# Charge_Station.net
KiCad netlist of a schematic drawn in Altium Designer
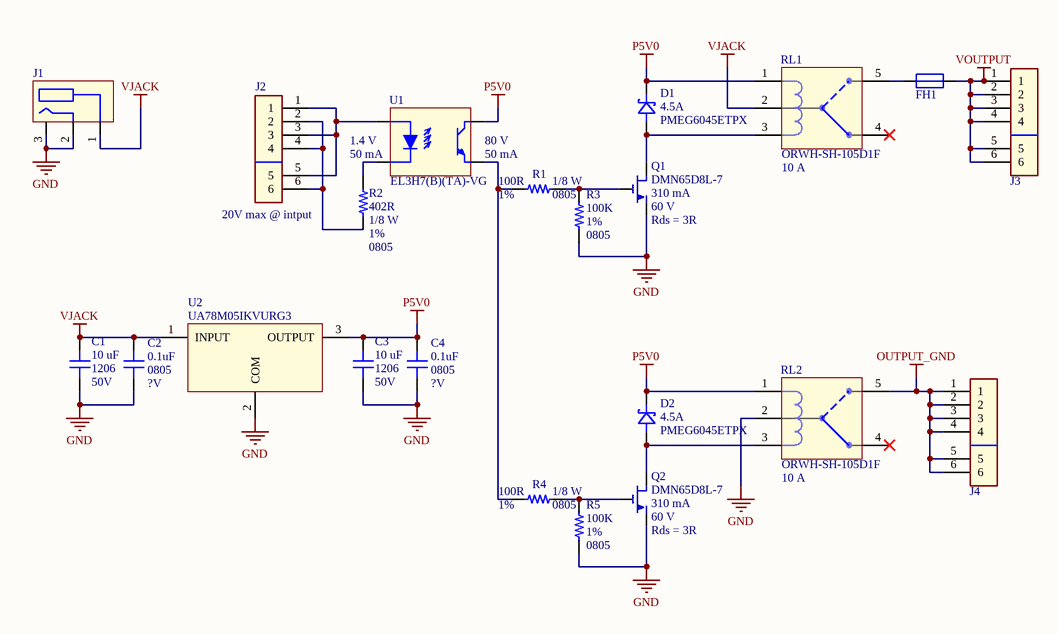
[diagram p0: Charge Station.SchDoc]

(export (version "E")
  (design (tool "Eeschema 10.0.6"))
  (components
    (comp (ref "C1")
      (value "10 uF")
      (footprint "CAP_1206")
      (description "CAP - 1206")
      (fields
        (field (name "PACKAGE") "1206")
        (field (name "VOLTAGE") "50V")
        (field (name "PART NUMBER") "GRT31CR61H106ME01L")
      )
      (libsource (lib "SecureBot") (part "CAP - 1206"))
    )
    (comp (ref "C2")
      (value "0.1uF")
      (footprint "CAP_0805")
      (description "CAP - 0805")
      (fields
        (field (name "PART NUMBER") "CC0805KRX7R9BB104")
        (field (name "PACKAGE") "0805")
        (field (name "VOLTAGE") "?V")
      )
      (libsource (lib "SecureBot") (part "CAP - 0805"))
    )
    (comp (ref "C3")
      (value "10 uF")
      (footprint "CAP_1206")
      (description "CAP - 1206")
      (fields
        (field (name "PACKAGE") "1206")
        (field (name "VOLTAGE") "50V")
        (field (name "PART NUMBER") "GRT31CR61H106ME01L")
      )
      (libsource (lib "SecureBot") (part "CAP - 1206"))
    )
    (comp (ref "C4")
      (value "0.1uF")
      (footprint "CAP_0805")
      (description "CAP - 0805")
      (fields
        (field (name "PART NUMBER") "CC0805KRX7R9BB104")
        (field (name "PACKAGE") "0805")
        (field (name "VOLTAGE") "?V")
      )
      (libsource (lib "SecureBot") (part "CAP - 0805"))
    )
    (comp (ref "D1")
      (value "SCHOTTKEY")
      (footprint "DO-214AC_SOD128")
      (fields (field (name "CURRENT") "4.5A") (field (name "PART NUMBER") "PMEG6045ETPX"))
      (libsource (lib "SecureBot") (part "SCHOTTKEY"))
    )
    (comp (ref "D2")
      (value "SCHOTTKEY")
      (footprint "DO-214AC_SOD128")
      (fields (field (name "CURRENT") "4.5A") (field (name "PART NUMBER") "PMEG6045ETPX"))
      (libsource (lib "SecureBot") (part "SCHOTTKEY"))
    )
    (comp (ref "FH1")
      (value "FH 3AB-3AG")
      (footprint "FH_3AB_3AG")
      (description "Fuse holder (3AB-3AG)")
      (fields (field (name "PART NUMBER") "01020071Z x2"))
      (libsource (lib "SecureBot") (part "FH 3AB-3AG"))
    )
    (comp (ref "J1")
      (value "Barrel 5.5x2.5mm")
      (footprint "Barrel 5.5mm 2.5mm")
      (description "Jack 5.5x2.5mm")
      (fields (field (name "PART NUMBER") "PJ-082BH"))
      (libsource (lib "SecureBot") (part "Barrel 5.5x2.5mm"))
    )
    (comp (ref "J2")
      (value "MOLEX 4 POS - TERMINAL BLOCK 2 POS")
      (footprint "MOLEX4POS_TERMBLOCK2POS")
      (fields (field (name "PART NUMBER") "0039281043") (field (name "PART NUMBER_1") "OSTOQ023250"))
      (libsource (lib "") (part "MOLEX 4 POS - TERMINAL BLOCK 2 POS_1"))
    )
    (comp (ref "J3")
      (value "MOLEX 4 POS - TERMINAL BLOCK 2 POS")
      (footprint "MOLEX4POS_TERMBLOCK2POS")
      (fields (field (name "PART NUMBER") "0039281043") (field (name "PART NUMBER_1") "OSTOQ023250"))
      (libsource (lib "SecureBot") (part "MOLEX 4 POS - TERMINAL BLOCK 2 POS"))
    )
    (comp (ref "J4")
      (value "MOLEX 4 POS - TERMINAL BLOCK 2 POS")
      (footprint "MOLEX4POS_TERMBLOCK2POS")
      (fields (field (name "PART NUMBER") "0039281043") (field (name "PART NUMBER_1") "OSTOQ023250"))
      (libsource (lib "SecureBot") (part "MOLEX 4 POS - TERMINAL BLOCK 2 POS"))
    )
    (comp (ref "Q1")
      (value "NMOS")
      (footprint "SOT-23")
      (fields
        (field (name "PART NUMBER") "DMN65D8L-7")
        (field (name "A MAX") "310 mA")
        (field (name "VDS MAX") "60 V")
        (field (name "RON") "Rds = 3R")
      )
      (libsource (lib "SecureBot") (part "NMOS"))
    )
    (comp (ref "Q2")
      (value "NMOS")
      (footprint "SOT-23")
      (fields
        (field (name "PART NUMBER") "DMN65D8L-7")
        (field (name "A MAX") "310 mA")
        (field (name "VDS MAX") "60 V")
        (field (name "RON") "Rds = 3R")
      )
      (libsource (lib "SecureBot") (part "NMOS"))
    )
    (comp (ref "R1")
      (value "100R")
      (footprint "RES_0805")
      (description "RES - 0805")
      (fields
        (field (name "PART NUMBER") "ERA-6AEB101V")
        (field (name "WATT") "1/8 W")
        (field (name "TOLERANCE") "1%")
        (field (name "PACKAGE") "0805")
      )
      (libsource (lib "SecureBot") (part "RES - 0805"))
    )
    (comp (ref "R2")
      (value "402R")
      (footprint "RES_0805")
      (description "RES - 0805")
      (fields
        (field (name "PART NUMBER") "ERA-6AEB4020V")
        (field (name "WATT") "1/8 W")
        (field (name "TOLERANCE") "1%")
        (field (name "PACKAGE") "0805")
      )
      (libsource (lib "SecureBot") (part "RES - 0805"))
    )
    (comp (ref "R3")
      (value "100K")
      (footprint "RES_0805")
      (description "RES - 0805")
      (fields
        (field (name "PART NUMBER") "RMCF0805FT100K")
        (field (name "TOLERANCE") "1%")
        (field (name "PACKAGE") "0805")
      )
      (libsource (lib "SecureBot") (part "RES - 0805"))
    )
    (comp (ref "R4")
      (value "100R")
      (footprint "RES_0805")
      (description "RES - 0805")
      (fields
        (field (name "PART NUMBER") "ERA-6AEB101V")
        (field (name "WATT") "1/8 W")
        (field (name "TOLERANCE") "1%")
        (field (name "PACKAGE") "0805")
      )
      (libsource (lib "SecureBot") (part "RES - 0805"))
    )
    (comp (ref "R5")
      (value "100K")
      (footprint "RES_0805")
      (description "RES - 0805")
      (fields
        (field (name "PART NUMBER") "RMCF0805FT100K")
        (field (name "TOLERANCE") "1%")
        (field (name "PACKAGE") "0805")
      )
      (libsource (lib "SecureBot") (part "RES - 0805"))
    )
    (comp (ref "RL1")
      (value "Relay SPDT")
      (footprint "ORWH-SH")
      (fields (field (name "PART NUMBER") "ORWH-SH-105D1F") (field (name "A MAX") "10 A"))
      (libsource (lib "SecureBot") (part "Relay SPDT"))
    )
    (comp (ref "RL2")
      (value "Relay SPDT")
      (footprint "ORWH-SH")
      (fields (field (name "PART NUMBER") "ORWH-SH-105D1F") (field (name "A MAX") "10 A"))
      (libsource (lib "SecureBot") (part "Relay SPDT"))
    )
    (comp (ref "U1")
      (value "Optoisolator")
      (footprint "SOIC127P700X200-4M")
      (fields
        (field (name "PART NUMBER") "EL3H7(B)(TA)-VG")
        (field (name "MAX VF") "1.4 V")
        (field (name "MAX OUTPUT CURRENT") "50 mA")
        (field (name "VOUTPUT MAX") "80 V")
        (field (name "MAX IF") "50 mA")
      )
      (libsource (lib "SecureBot") (part "Optoisolator"))
    )
    (comp (ref "U2")
      (value "UA78M")
      (footprint "DPAK229P991X252-3N")
      (fields (field (name "PART NUMBER") "UA78M05IKVURG3"))
      (libsource (lib "SecureBot") (part "UA78M"))
    )
  )
  (nets
    (net (code "1") (name "GND") (class "Default")
      (node (ref "C1") (pin "2") (pinfunction "2_2") (pintype "passive"))
      (node (ref "C2") (pin "2") (pinfunction "2_2") (pintype "passive"))
      (node (ref "C3") (pin "2") (pinfunction "2_2") (pintype "passive"))
      (node (ref "C4") (pin "2") (pinfunction "2_2") (pintype "passive"))
      (node (ref "J1") (pin "2") (pinfunction "2_2") (pintype "passive"))
      (node (ref "J1") (pin "3") (pinfunction "3_3") (pintype "passive"))
      (node (ref "Q1") (pin "1") (pinfunction "1_1") (pintype "passive"))
      (node (ref "Q2") (pin "1") (pinfunction "1_1") (pintype "passive"))
      (node (ref "R3") (pin "1") (pinfunction "1_1") (pintype "passive"))
      (node (ref "R5") (pin "1") (pinfunction "1_1") (pintype "passive"))
      (node (ref "RL2") (pin "2") (pinfunction "2_2") (pintype "passive"))
      (node (ref "U2") (pin "2") (pinfunction "COM_2") (pintype "passive"))
    )
    (net (code "2") (name "Net-(D1-Pad1)") (class "Default")
      (node (ref "D1") (pin "1") (pinfunction "1_1") (pintype "passive"))
      (node (ref "Q1") (pin "3") (pinfunction "3_3") (pintype "passive"))
      (node (ref "RL1") (pin "3") (pinfunction "3_3") (pintype "passive"))
    )
    (net (code "3") (name "Net-(D2-Pad1)") (class "Default")
      (node (ref "D2") (pin "1") (pinfunction "1_1") (pintype "passive"))
      (node (ref "Q2") (pin "3") (pinfunction "3_3") (pintype "passive"))
      (node (ref "RL2") (pin "3") (pinfunction "3_3") (pintype "passive"))
    )
    (net (code "4") (name "Net-(FH1-Pad2)") (class "Default")
      (node (ref "FH1") (pin "2") (pinfunction "2_2") (pintype "passive"))
      (node (ref "RL1") (pin "5") (pinfunction "5_5") (pintype "passive"))
    )
    (net (code "5") (name "Net-(J2-Pad1)") (class "Default")
      (node (ref "J2") (pin "1") (pinfunction "1_1") (pintype "passive"))
      (node (ref "J2") (pin "3") (pinfunction "3_3") (pintype "passive"))
      (node (ref "J2") (pin "5") (pinfunction "5_5") (pintype "passive"))
      (node (ref "U1") (pin "1") (pinfunction "1_1") (pintype "passive"))
    )
    (net (code "6") (name "Net-(J2-Pad2)") (class "Default")
      (node (ref "J2") (pin "2") (pinfunction "2_2") (pintype "passive"))
      (node (ref "J2") (pin "4") (pinfunction "4_4") (pintype "passive"))
      (node (ref "J2") (pin "6") (pinfunction "6_6") (pintype "passive"))
      (node (ref "R2") (pin "1") (pinfunction "1_1") (pintype "passive"))
    )
    (net (code "7") (name "Net-(Q1-Pad2)") (class "Default")
      (node (ref "Q1") (pin "2") (pinfunction "2_2") (pintype "passive"))
      (node (ref "R1") (pin "2") (pinfunction "2_2") (pintype "passive"))
      (node (ref "R3") (pin "2") (pinfunction "2_2") (pintype "passive"))
    )
    (net (code "8") (name "Net-(Q2-Pad2)") (class "Default")
      (node (ref "Q2") (pin "2") (pinfunction "2_2") (pintype "passive"))
      (node (ref "R4") (pin "2") (pinfunction "2_2") (pintype "passive"))
      (node (ref "R5") (pin "2") (pinfunction "2_2") (pintype "passive"))
    )
    (net (code "9") (name "Net-(R1-Pad1)") (class "Default")
      (node (ref "R1") (pin "1") (pinfunction "1_1") (pintype "passive"))
      (node (ref "R4") (pin "1") (pinfunction "1_1") (pintype "passive"))
      (node (ref "U1") (pin "3") (pinfunction "3_3") (pintype "passive"))
    )
    (net (code "10") (name "Net-(R2-Pad2)") (class "Default")
      (node (ref "R2") (pin "2") (pinfunction "2_2") (pintype "passive"))
      (node (ref "U1") (pin "2") (pinfunction "2_2") (pintype "passive"))
    )
    (net (code "11") (name "OUTPUT_GND") (class "Default")
      (node (ref "J4") (pin "1") (pinfunction "1_1") (pintype "passive"))
      (node (ref "J4") (pin "2") (pinfunction "2_2") (pintype "passive"))
      (node (ref "J4") (pin "3") (pinfunction "3_3") (pintype "passive"))
      (node (ref "J4") (pin "4") (pinfunction "4_4") (pintype "passive"))
      (node (ref "J4") (pin "5") (pinfunction "5_5") (pintype "passive"))
      (node (ref "J4") (pin "6") (pinfunction "6_6") (pintype "passive"))
      (node (ref "RL2") (pin "5") (pinfunction "5_5") (pintype "passive"))
    )
    (net (code "12") (name "P5V0") (class "Default")
      (node (ref "C3") (pin "1") (pinfunction "1_1") (pintype "passive"))
      (node (ref "C4") (pin "1") (pinfunction "1_1") (pintype "passive"))
      (node (ref "D1") (pin "2") (pinfunction "2_2") (pintype "passive"))
      (node (ref "D2") (pin "2") (pinfunction "2_2") (pintype "passive"))
      (node (ref "RL1") (pin "1") (pinfunction "1_1") (pintype "passive"))
      (node (ref "RL2") (pin "1") (pinfunction "1_1") (pintype "passive"))
      (node (ref "U1") (pin "4") (pinfunction "4_4") (pintype "passive"))
      (node (ref "U2") (pin "3") (pinfunction "OUTPUT_3") (pintype "passive"))
    )
    (net (code "13") (name "VJACK") (class "Default")
      (node (ref "C1") (pin "1") (pinfunction "1_1") (pintype "passive"))
      (node (ref "C2") (pin "1") (pinfunction "1_1") (pintype "passive"))
      (node (ref "J1") (pin "1") (pinfunction "1_1") (pintype "passive"))
      (node (ref "RL1") (pin "2") (pinfunction "2_2") (pintype "passive"))
      (node (ref "U2") (pin "1") (pinfunction "INPUT_1") (pintype "passive"))
    )
    (net (code "14") (name "VOUTPUT") (class "Default")
      (node (ref "FH1") (pin "1") (pinfunction "1_1") (pintype "passive"))
      (node (ref "J3") (pin "1") (pinfunction "1_1") (pintype "passive"))
      (node (ref "J3") (pin "2") (pinfunction "2_2") (pintype "passive"))
      (node (ref "J3") (pin "3") (pinfunction "3_3") (pintype "passive"))
      (node (ref "J3") (pin "4") (pinfunction "4_4") (pintype "passive"))
      (node (ref "J3") (pin "5") (pinfunction "5_5") (pintype "passive"))
      (node (ref "J3") (pin "6") (pinfunction "6_6") (pintype "passive"))
    )
    (net (code "15") (name "unconnected-(RL1-Pad4)") (class "Default")
      (node (ref "RL1") (pin "4") (pinfunction "4_4") (pintype "passive+no_connect"))
    )
    (net (code "16") (name "unconnected-(RL2-Pad4)") (class "Default")
      (node (ref "RL2") (pin "4") (pinfunction "4_4") (pintype "passive+no_connect"))
    )
  )
)
